# IO.net
KiCad netlist of a schematic drawn in Altium Designer
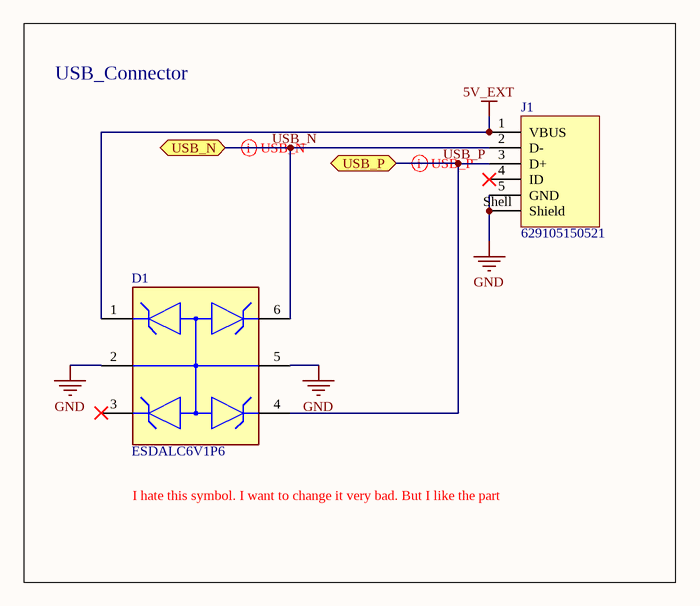
[diagram p0: IO.SchDoc]

(export (version "E")
  (design (tool "Eeschema 10.0.6"))
  (components
    (comp (ref "D1")
      (value "ESDALC6V1P6")
      (footprint "FP-SOT-666IP-MFG")
      (description "4 Channel 6.1V Uni-Directional Transil ESD Protection - SOT-666IP")
      (fields (field (name "MANUFACTURER") "STMicroelectronics"))
      (libsource (lib "Altium Content Vault") (part "6a900b17cb0463f8823600865c9f9ee"))
    )
    (comp (ref "J1")
      (value "629105150521")
      (footprint "629105150521")
      (libsource (lib "Altium Content Vault") (part "Micro USB 2.0_Type B_Receptacle_1 Port"))
    )
  )
  (nets
    (net (code "1") (name "/USB_N") (class "Default")
      (node (ref "D1") (pin "6") (pinfunction "6_6") (pintype "passive"))
      (node (ref "J1") (pin "2") (pinfunction "D-_2") (pintype "passive"))
    )
    (net (code "2") (name "/USB_P") (class "Default")
      (node (ref "D1") (pin "4") (pinfunction "4_4") (pintype "passive"))
      (node (ref "J1") (pin "3") (pinfunction "D+_3") (pintype "passive"))
    )
    (net (code "3") (name "5V_EXT") (class "Default")
      (node (ref "D1") (pin "1") (pinfunction "1_1") (pintype "passive"))
      (node (ref "J1") (pin "1") (pinfunction "VBUS_1") (pintype "passive"))
    )
    (net (code "4") (name "GND") (class "Default")
      (node (ref "D1") (pin "2") (pinfunction "2_2") (pintype "passive"))
      (node (ref "D1") (pin "5") (pinfunction "5_5") (pintype "passive"))
      (node (ref "J1") (pin "5") (pinfunction "GND_5") (pintype "passive"))
      (node (ref "J1") (pin "Shell") (pinfunction "Shield_Shell") (pintype "passive"))
    )
    (net (code "5") (name "unconnected-(D1-Pad3)") (class "Default")
      (node (ref "D1") (pin "3") (pinfunction "3_3") (pintype "passive+no_connect"))
    )
    (net (code "6") (name "unconnected-(J1-ID-Pad4)") (class "Default")
      (node (ref "J1") (pin "4") (pinfunction "ID_4") (pintype "passive+no_connect"))
    )
  )
)
